# Attiny84_PIR_RELE.net
KiCad netlist of a schematic drawn in EAGLE
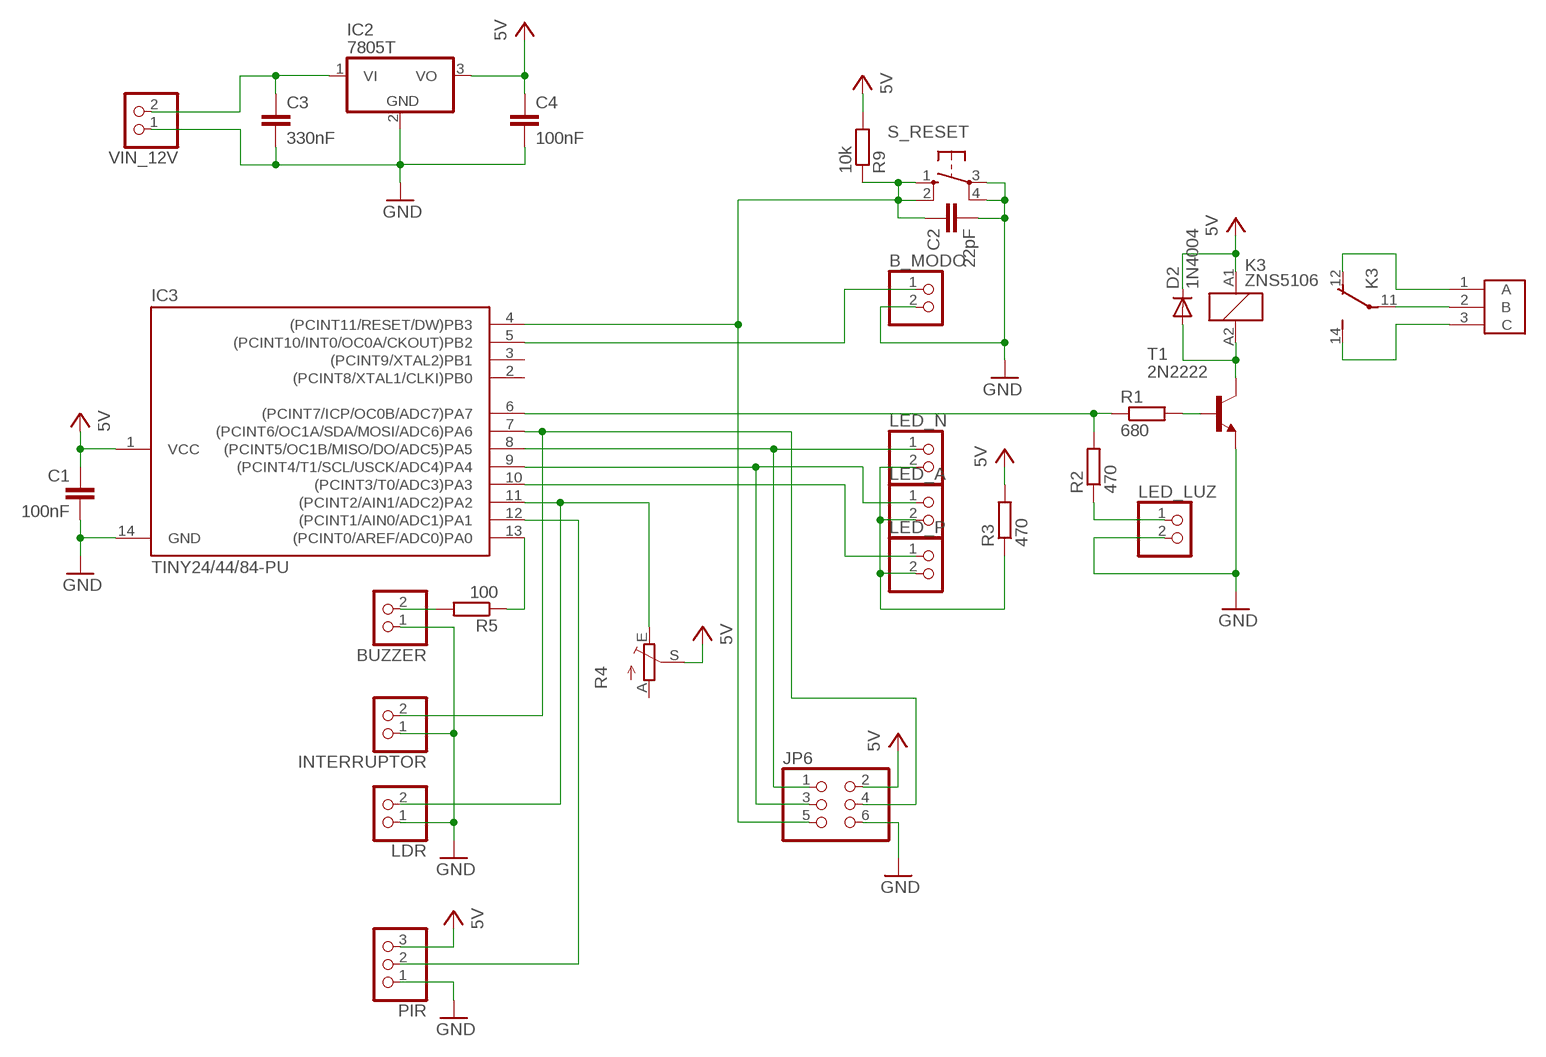
[diagram p0: schematic, sheet 1]

(export (version "E")
  (design (tool "Eeschema 10.0.6"))
  (components
    (comp (ref "BUZZER")
      (value "PINHD-1X2")
      (footprint "eagle-import:1X02")
      (libsource (lib "eagle-import") (part "PINHD-1X2"))
    )
    (comp (ref "B_MODO")
      (value "PINHD-1X2")
      (footprint "eagle-import:1X02")
      (libsource (lib "eagle-import") (part "PINHD-1X2"))
    )
    (comp (ref "C1")
      (value "100nF")
      (footprint "eagle-import:C050-025X075")
      (libsource (lib "eagle-import") (part "C-EU050-025X075"))
    )
    (comp (ref "C2")
      (value "22pF")
      (footprint "eagle-import:C050-025X075")
      (libsource (lib "eagle-import") (part "C-EU050-025X075"))
    )
    (comp (ref "C3")
      (value "330nF")
      (footprint "eagle-import:C050-025X075")
      (libsource (lib "eagle-import") (part "C-EU050-025X075"))
    )
    (comp (ref "C4")
      (value "100nF")
      (footprint "eagle-import:C050-025X075")
      (libsource (lib "eagle-import") (part "C-EU050-025X075"))
    )
    (comp (ref "D2")
      (value "1N4004")
      (footprint "eagle-import:DO41-10")
      (libsource (lib "eagle-import") (part "1N4004"))
    )
    (comp (ref "IC2")
      (value "7805T")
      (footprint "eagle-import:TO220H")
      (libsource (lib "eagle-import") (part "78T05"))
    )
    (comp (ref "IC3")
      (value "TINY24/44/84-PU")
      (footprint "eagle-import:DIL14")
      (libsource (lib "eagle-import") (part "TINY24/44/84-PU"))
    )
    (comp (ref "INTERRUPTOR")
      (value "PINHD-1X2")
      (footprint "eagle-import:1X02")
      (libsource (lib "eagle-import") (part "PINHD-1X2"))
    )
    (comp (ref "JP6")
      (value "PINHD-2X3")
      (footprint "eagle-import:2X03")
      (libsource (lib "eagle-import") (part "PINHD-2X3"))
    )
    (comp (ref "K3")
      (value "ZNS5106")
      (footprint "eagle-import:ZN5")
      (libsource (lib "eagle-import") (part "ZNS5106"))
    )
    (comp (ref "LDR")
      (value "PINHD-1X2")
      (footprint "eagle-import:1X02")
      (libsource (lib "eagle-import") (part "PINHD-1X2"))
    )
    (comp (ref "LED_A")
      (value "PINHD-1X2")
      (footprint "eagle-import:1X02")
      (libsource (lib "eagle-import") (part "PINHD-1X2"))
    )
    (comp (ref "LED_LUZ")
      (value "PINHD-1X2")
      (footprint "eagle-import:1X02")
      (libsource (lib "eagle-import") (part "PINHD-1X2"))
    )
    (comp (ref "LED_N")
      (value "PINHD-1X2")
      (footprint "eagle-import:1X02")
      (libsource (lib "eagle-import") (part "PINHD-1X2"))
    )
    (comp (ref "LED_P")
      (value "PINHD-1X2")
      (footprint "eagle-import:1X02")
      (libsource (lib "eagle-import") (part "PINHD-1X2"))
    )
    (comp (ref "PIR")
      (value "PINHD-1X3")
      (footprint "eagle-import:1X03")
      (libsource (lib "eagle-import") (part "PINHD-1X3"))
    )
    (comp (ref "R1")
      (value "680")
      (footprint "eagle-import:0204_7")
      (libsource (lib "eagle-import") (part "R-EU_0204/7"))
    )
    (comp (ref "R2")
      (value "470")
      (footprint "eagle-import:0204_7")
      (libsource (lib "eagle-import") (part "R-EU_0204/7"))
    )
    (comp (ref "R3")
      (value "470")
      (footprint "eagle-import:0204_7")
      (libsource (lib "eagle-import") (part "R-EU_0204/7"))
    )
    (comp (ref "R4")
      (value "TRIM_EU-LI10")
      (footprint "eagle-import:LI10")
      (libsource (lib "eagle-import") (part "TRIM_EU-LI10"))
    )
    (comp (ref "R5")
      (value "100")
      (footprint "eagle-import:0204_7")
      (libsource (lib "eagle-import") (part "R-EU_0204/7"))
    )
    (comp (ref "R9")
      (value "10k")
      (footprint "eagle-import:0204_7")
      (libsource (lib "eagle-import") (part "R-EU_0204/7"))
    )
    (comp (ref "S_RESET")
      (value "10-XX")
      (footprint "eagle-import:B3F-10XX")
      (fields (field (name "MPN") "B3F-1000"))
      (libsource (lib "eagle-import") (part "10-XX"))
    )
    (comp (ref "T1")
      (value "2N2222")
      (footprint "eagle-import:TO18")
      (libsource (lib "eagle-import") (part "2N2222"))
    )
    (comp (ref "U$1")
      (value "POT_CONNECTOR")
      (footprint "eagle-import:POT_CONNECTOR")
      (libsource (lib "eagle-import") (part "POT_CONNECTOR"))
    )
    (comp (ref "VIN_12V")
      (value "PINHD-1X2")
      (footprint "eagle-import:1X02")
      (libsource (lib "eagle-import") (part "PINHD-1X2"))
    )
  )
  (nets
    (net (code "1") (name "5V") (class "Default")
      (node (ref "C1") (pin "1") (pinfunction "1_1") (pintype "passive"))
      (node (ref "C4") (pin "1") (pinfunction "1_1") (pintype "passive"))
      (node (ref "D2") (pin "C") (pinfunction "C_C") (pintype "passive"))
      (node (ref "IC2") (pin "3") (pinfunction "VO_3") (pintype "passive"))
      (node (ref "IC3") (pin "1") (pinfunction "VCC_1") (pintype "power_in"))
      (node (ref "JP6") (pin "2") (pinfunction "2_2") (pintype "passive"))
      (node (ref "K3") (pin "A1") (pinfunction "1_A1") (pintype "passive"))
      (node (ref "PIR") (pin "3") (pinfunction "3_3") (pintype "passive"))
      (node (ref "R3") (pin "2") (pinfunction "2_2") (pintype "passive"))
      (node (ref "R4") (pin "S") (pinfunction "S_S") (pintype "passive"))
      (node (ref "R9") (pin "2") (pinfunction "2_2") (pintype "passive"))
    )
    (net (code "2") (name "GND") (class "Default")
      (node (ref "BUZZER") (pin "1") (pinfunction "1_1") (pintype "passive"))
      (node (ref "B_MODO") (pin "2") (pinfunction "2_2") (pintype "passive"))
      (node (ref "C1") (pin "2") (pinfunction "2_2") (pintype "passive"))
      (node (ref "C2") (pin "2") (pinfunction "2_2") (pintype "passive"))
      (node (ref "C3") (pin "2") (pinfunction "2_2") (pintype "passive"))
      (node (ref "C4") (pin "2") (pinfunction "2_2") (pintype "passive"))
      (node (ref "IC2") (pin "2") (pinfunction "GND_2") (pintype "passive"))
      (node (ref "IC3") (pin "14") (pinfunction "GND_14") (pintype "power_in"))
      (node (ref "INTERRUPTOR") (pin "1") (pinfunction "1_1") (pintype "passive"))
      (node (ref "JP6") (pin "6") (pinfunction "6_6") (pintype "passive"))
      (node (ref "LDR") (pin "1") (pinfunction "1_1") (pintype "passive"))
      (node (ref "LED_LUZ") (pin "2") (pinfunction "2_2") (pintype "passive"))
      (node (ref "PIR") (pin "1") (pinfunction "1_1") (pintype "passive"))
      (node (ref "S_RESET") (pin "3") (pinfunction "P_3") (pintype "passive"))
      (node (ref "S_RESET") (pin "4") (pinfunction "P1_4") (pintype "passive"))
      (node (ref "T1") (pin "1") (pinfunction "E_1") (pintype "passive"))
      (node (ref "VIN_12V") (pin "1") (pinfunction "1_1") (pintype "passive"))
    )
    (net (code "3") (name "Net-(BUZZER-Pad2)") (class "Default")
      (node (ref "BUZZER") (pin "2") (pinfunction "2_2") (pintype "passive"))
      (node (ref "R5") (pin "2") (pinfunction "2_2") (pintype "passive"))
    )
    (net (code "4") (name "Net-(IC2-VI)") (class "Default")
      (node (ref "C3") (pin "1") (pinfunction "1_1") (pintype "passive"))
      (node (ref "IC2") (pin "1") (pinfunction "VI_1") (pintype "input"))
      (node (ref "VIN_12V") (pin "2") (pinfunction "2_2") (pintype "passive"))
    )
    (net (code "5") (name "Net-(IC3-(PCINT0{slash}AREF{slash}ADC0)PA0)") (class "Default")
      (node (ref "IC3") (pin "13") (pinfunction "(PCINT0/AREF/ADC0)PA0_13") (pintype "bidirectional"))
      (node (ref "R5") (pin "1") (pinfunction "1_1") (pintype "passive"))
    )
    (net (code "6") (name "Net-(IC3-(PCINT1{slash}AIN0{slash}ADC1)PA1)") (class "Default")
      (node (ref "IC3") (pin "12") (pinfunction "(PCINT1/AIN0/ADC1)PA1_12") (pintype "bidirectional"))
      (node (ref "PIR") (pin "2") (pinfunction "2_2") (pintype "passive"))
    )
    (net (code "7") (name "Net-(IC3-(PCINT2{slash}AIN1{slash}ADC2)PA2)") (class "Default")
      (node (ref "IC3") (pin "11") (pinfunction "(PCINT2/AIN1/ADC2)PA2_11") (pintype "bidirectional"))
      (node (ref "LDR") (pin "2") (pinfunction "2_2") (pintype "passive"))
      (node (ref "R4") (pin "E") (pinfunction "E_E") (pintype "passive"))
    )
    (net (code "8") (name "Net-(IC3-(PCINT3{slash}T0{slash}ADC3)PA3)") (class "Default")
      (node (ref "IC3") (pin "10") (pinfunction "(PCINT3/T0/ADC3)PA3_10") (pintype "bidirectional"))
      (node (ref "LED_P") (pin "1") (pinfunction "1_1") (pintype "passive"))
    )
    (net (code "9") (name "Net-(IC3-(PCINT4{slash}T1{slash}SCL{slash}USCK{slash}ADC4)PA4)") (class "Default")
      (node (ref "IC3") (pin "9") (pinfunction "(PCINT4/T1/SCL/USCK/ADC4)PA4_9") (pintype "bidirectional"))
      (node (ref "JP6") (pin "3") (pinfunction "3_3") (pintype "passive"))
      (node (ref "LED_A") (pin "1") (pinfunction "1_1") (pintype "passive"))
    )
    (net (code "10") (name "Net-(IC3-(PCINT5{slash}OC1B{slash}MISO{slash}DO{slash}ADC5)PA5)") (class "Default")
      (node (ref "IC3") (pin "8") (pinfunction "(PCINT5/OC1B/MISO/DO/ADC5)PA5_8") (pintype "bidirectional"))
      (node (ref "JP6") (pin "1") (pinfunction "1_1") (pintype "passive"))
      (node (ref "LED_N") (pin "1") (pinfunction "1_1") (pintype "passive"))
    )
    (net (code "11") (name "Net-(IC3-(PCINT6{slash}OC1A{slash}SDA{slash}MOSI{slash}ADC6)PA6)") (class "Default")
      (node (ref "IC3") (pin "7") (pinfunction "(PCINT6/OC1A/SDA/MOSI/ADC6)PA6_7") (pintype "bidirectional"))
      (node (ref "INTERRUPTOR") (pin "2") (pinfunction "2_2") (pintype "passive"))
      (node (ref "JP6") (pin "4") (pinfunction "4_4") (pintype "passive"))
    )
    (net (code "12") (name "Net-(IC3-(PCINT7{slash}ICP{slash}OC0B{slash}ADC7)PA7)") (class "Default")
      (node (ref "IC3") (pin "6") (pinfunction "(PCINT7/ICP/OC0B/ADC7)PA7_6") (pintype "bidirectional"))
      (node (ref "R1") (pin "1") (pinfunction "1_1") (pintype "passive"))
      (node (ref "R2") (pin "2") (pinfunction "2_2") (pintype "passive"))
    )
    (net (code "13") (name "Net-(IC3-(PCINT10{slash}INT0{slash}OC0A{slash}CKOUT)PB2)") (class "Default")
      (node (ref "B_MODO") (pin "1") (pinfunction "1_1") (pintype "passive"))
      (node (ref "IC3") (pin "5") (pinfunction "(PCINT10/INT0/OC0A/CKOUT)PB2_5") (pintype "bidirectional"))
    )
    (net (code "14") (name "Net-(IC3-(PCINT11{slash}RESET{slash}DW)PB3)") (class "Default")
      (node (ref "C2") (pin "1") (pinfunction "1_1") (pintype "passive"))
      (node (ref "IC3") (pin "4") (pinfunction "(PCINT11/RESET/DW)PB3_4") (pintype "bidirectional"))
      (node (ref "JP6") (pin "5") (pinfunction "5_5") (pintype "passive"))
      (node (ref "R9") (pin "1") (pinfunction "1_1") (pintype "passive"))
      (node (ref "S_RESET") (pin "1") (pinfunction "S_1") (pintype "passive"))
      (node (ref "S_RESET") (pin "2") (pinfunction "S1_2") (pintype "passive"))
    )
    (net (code "15") (name "Net-(K3A-2)") (class "Default")
      (node (ref "D2") (pin "A") (pinfunction "A_A") (pintype "passive"))
      (node (ref "K3") (pin "A2") (pinfunction "2_A2") (pintype "passive"))
      (node (ref "T1") (pin "3") (pinfunction "C_3") (pintype "passive"))
    )
    (net (code "16") (name "Net-(K3B-O)") (class "Default")
      (node (ref "K3") (pin "12") (pinfunction "O_12") (pintype "passive"))
      (node (ref "U$1") (pin "1") (pinfunction "A_1") (pintype "bidirectional"))
    )
    (net (code "17") (name "Net-(K3B-P)") (class "Default")
      (node (ref "K3") (pin "11") (pinfunction "P_11") (pintype "passive"))
      (node (ref "U$1") (pin "2") (pinfunction "B_2") (pintype "bidirectional"))
    )
    (net (code "18") (name "Net-(K3B-S)") (class "Default")
      (node (ref "K3") (pin "14") (pinfunction "S_14") (pintype "passive"))
      (node (ref "U$1") (pin "3") (pinfunction "C_3") (pintype "bidirectional"))
    )
    (net (code "19") (name "Net-(LED_A-Pad2)") (class "Default")
      (node (ref "LED_A") (pin "2") (pinfunction "2_2") (pintype "passive"))
      (node (ref "LED_N") (pin "2") (pinfunction "2_2") (pintype "passive"))
      (node (ref "LED_P") (pin "2") (pinfunction "2_2") (pintype "passive"))
      (node (ref "R3") (pin "1") (pinfunction "1_1") (pintype "passive"))
    )
    (net (code "20") (name "Net-(LED_LUZ-Pad1)") (class "Default")
      (node (ref "LED_LUZ") (pin "1") (pinfunction "1_1") (pintype "passive"))
      (node (ref "R2") (pin "1") (pinfunction "1_1") (pintype "passive"))
    )
    (net (code "21") (name "Net-(T1-B)") (class "Default")
      (node (ref "R1") (pin "2") (pinfunction "2_2") (pintype "passive"))
      (node (ref "T1") (pin "2") (pinfunction "B_2") (pintype "passive"))
    )
    (net (code "22") (name "unconnected-(IC3-(PCINT8{slash}XTAL1{slash}CLKI)PB0-Pad2)") (class "Default")
      (node (ref "IC3") (pin "2") (pinfunction "(PCINT8/XTAL1/CLKI)PB0_2") (pintype "bidirectional"))
    )
    (net (code "23") (name "unconnected-(IC3-(PCINT9{slash}XTAL2)PB1-Pad3)") (class "Default")
      (node (ref "IC3") (pin "3") (pinfunction "(PCINT9/XTAL2)PB1_3") (pintype "bidirectional"))
    )
    (net (code "24") (name "unconnected-(R4-PadA)") (class "Default")
      (node (ref "R4") (pin "A") (pinfunction "A_A") (pintype "passive"))
    )
  )
)
